# Microcontroller.net
KiCad netlist of a schematic drawn in Altium Designer
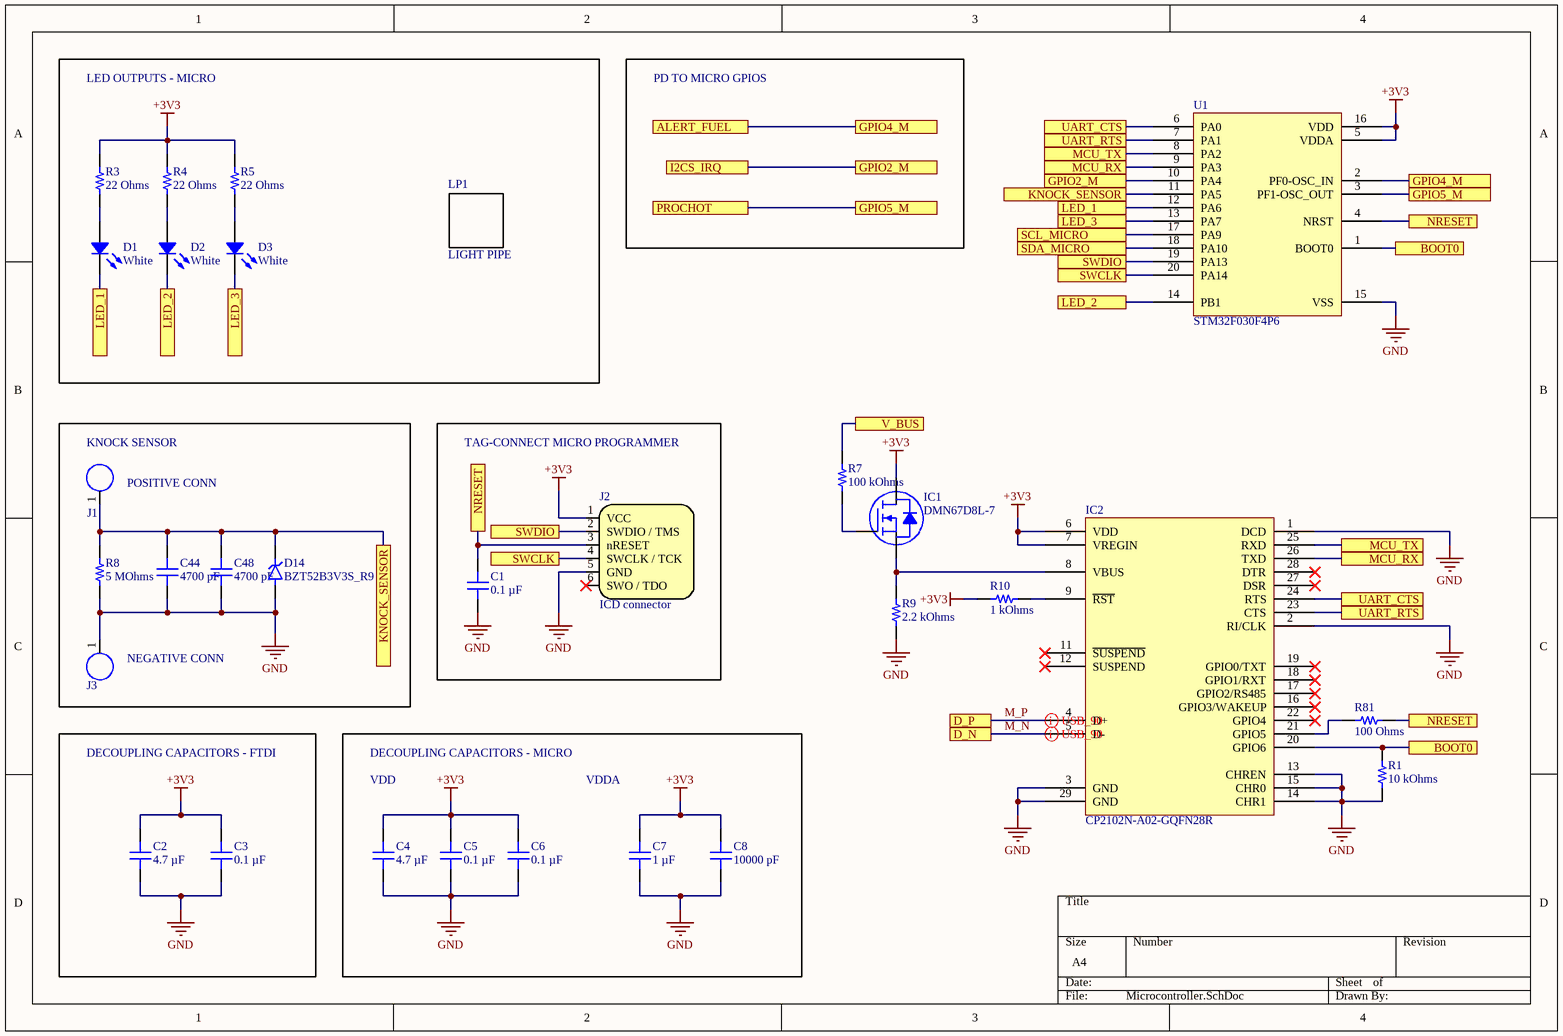
[diagram p0: Microcontroller.SchDoc]

(export (version "E")
  (design (tool "Eeschema 10.0.6"))
  (components
    (comp (ref "C1")
      (value "0.1 µF")
      (footprint "CAP 0402_1005")
      (description "CAP CER 0.1UF 10V X5R 0402")
      (fields (field (name "PART NUMBER") "LMK105BJ104MC-F") (field (name "MANUFACTURER") "Taiyo Yuden"))
      (libsource (lib "Celestial Altium Library - altium_library") (part "Capacitor"))
    )
    (comp (ref "C2")
      (value "4.7 µF")
      (footprint "CAP 0402_1005")
      (description "CAP CER 4.7UF 10V X5R 0402")
      (fields
        (field (name "PART NUMBER") "CL05A475KP5NRNC")
        (field (name "MANUFACTURER") "Samsung Electro-Mechanics")
      )
      (libsource (lib "Celestial Altium Library - altium_library") (part "Capacitor"))
    )
    (comp (ref "C3")
      (value "0.1 µF")
      (footprint "CAP 0402_1005")
      (description "CAP CER 0.1UF 10V X5R 0402")
      (fields (field (name "PART NUMBER") "LMK105BJ104MC-F") (field (name "MANUFACTURER") "Taiyo Yuden"))
      (libsource (lib "Celestial Altium Library - altium_library") (part "Capacitor"))
    )
    (comp (ref "C4")
      (value "4.7 µF")
      (footprint "CAP 0402_1005")
      (description "CAP CER 4.7UF 10V X5R 0402")
      (fields
        (field (name "PART NUMBER") "CL05A475KP5NRNC")
        (field (name "MANUFACTURER") "Samsung Electro-Mechanics")
      )
      (libsource (lib "Celestial Altium Library - altium_library") (part "Capacitor"))
    )
    (comp (ref "C5")
      (value "0.1 µF")
      (footprint "CAP 0402_1005")
      (description "CAP CER 0.1UF 10V X5R 0402")
      (fields (field (name "PART NUMBER") "LMK105BJ104MC-F") (field (name "MANUFACTURER") "Taiyo Yuden"))
      (libsource (lib "Celestial Altium Library - altium_library") (part "Capacitor"))
    )
    (comp (ref "C6")
      (value "0.1 µF")
      (footprint "CAP 0402_1005")
      (description "CAP CER 0.1UF 10V X5R 0402")
      (fields (field (name "PART NUMBER") "LMK105BJ104MC-F") (field (name "MANUFACTURER") "Taiyo Yuden"))
      (libsource (lib "Celestial Altium Library - altium_library") (part "Capacitor"))
    )
    (comp (ref "C7")
      (value "1 µF")
      (footprint "CAP 0402_1005")
      (description "CAP CER 1UF 10V X5R 0402")
      (fields (field (name "PART NUMBER") "LMK105BJ105KPLF") (field (name "MANUFACTURER") "Taiyo Yuden"))
      (libsource (lib "Celestial Altium Library - altium_library") (part "Capacitor"))
    )
    (comp (ref "C8")
      (value "10000 pF")
      (footprint "CAP 0402_1005")
      (description "CAP, MLCC, 0402/1005, 10V, X7R,")
      (fields (field (name "PART NUMBER") "LMF105B7103KVHF") (field (name "MANUFACTURER") "Taiyo Yuden"))
      (libsource (lib "Celestial Altium Library - altium_library") (part "Capacitor"))
    )
    (comp (ref "C44")
      (value "4700 pF")
      (footprint "CAP 0402_1005")
      (description "CAP CER 4700PF 50V X7R 0402")
      (fields
        (field (name "PART NUMBER") "0402B472J500CT")
        (field (name "MANUFACTURER") "Walsin Technology Corporation")
      )
      (libsource (lib "Celestial Altium Library - altium_library") (part "Capacitor"))
    )
    (comp (ref "C48")
      (value "4700 pF")
      (footprint "CAP 0402_1005")
      (description "CAP CER 4700PF 50V X7R 0402")
      (fields
        (field (name "PART NUMBER") "0402B472J500CT")
        (field (name "MANUFACTURER") "Walsin Technology Corporation")
      )
      (libsource (lib "Celestial Altium Library - altium_library") (part "Capacitor"))
    )
    (comp (ref "D1")
      (value "White")
      (footprint "LED 0805_2012")
      (description "0805 LED WHITE, YELLOW DIFFUSED")
      (fields (field (name "PART NUMBER") "QBLP631-IW5") (field (name "MANUFACTURER") "QT Brightek (QTB)"))
      (libsource (lib "Celestial Altium Library - altium_library") (part "LED"))
    )
    (comp (ref "D2")
      (value "White")
      (footprint "LED 0805_2012")
      (description "0805 LED WHITE, YELLOW DIFFUSED")
      (fields (field (name "PART NUMBER") "QBLP631-IW5") (field (name "MANUFACTURER") "QT Brightek (QTB)"))
      (libsource (lib "Celestial Altium Library - altium_library") (part "LED"))
    )
    (comp (ref "D3")
      (value "White")
      (footprint "LED 0805_2012")
      (description "0805 LED WHITE, YELLOW DIFFUSED")
      (fields (field (name "PART NUMBER") "QBLP631-IW5") (field (name "MANUFACTURER") "QT Brightek (QTB)"))
      (libsource (lib "Celestial Altium Library - altium_library") (part "LED"))
    )
    (comp (ref "D14")
      (value "BZT52B3V3S_R9")
      (footprint "BZT52B3V3S R9:DIO_BZT52B3V3S_R9")
      (fields (field (name "MF") "{'manufacturer': u'Taiwan Semiconductor'}"))
      (libsource (lib "*") (part "BZT52B3V3S_R9"))
    )
    (comp (ref "IC1")
      (value "DMN67D8L-7")
      (footprint "DIODES SOT-23-3")
      (description "MOSFET N-CH 60V 210MA SOT23")
      (fields (field (name "MANUFACTURER") "Diodes Incorporated"))
      (libsource (lib "Celestial Altium Library - altium_library") (part "DIODES INC MOSFET N-CH SOT-23-3"))
    )
    (comp (ref "IC2")
      (value "CP2102N-A02-GQFN28R")
      (footprint "SILICON LABS QFN-28 5x5MM")
      (description "IC USB TO UART BRIDGE QFN28")
      (fields (field (name "MANUFACTURER") "Silicon Labs"))
      (libsource (lib "Celestial Altium Library - altium_library") (part "Silicon Labs - CP2102N QFN28"))
    )
    (comp (ref "J1")
      (value "Large Board Solder Point")
      (footprint "Large Solder Point")
      (libsource (lib "Schlib2") (part "Large Board Solder Point"))
    )
    (comp (ref "J2")
      (value "ICD connector")
      (footprint "TC2030-MCP")
      (description "Conector par ICD")
      (libsource (lib "TC2030") (part "TC2030-MCP-NL"))
    )
    (comp (ref "J3")
      (value "Large Board Solder Point")
      (footprint "Large Solder Point")
      (libsource (lib "Schlib2") (part "Large Board Solder Point"))
    )
    (comp (ref "LP1")
      (value "LIGHT PIPE")
      (footprint "Dialight 515-1069F")
      (description "Light Pipe Dialight 515-1069F")
      (libsource (lib "Schlib2") (part "Dialight 515-1069F"))
    )
    (comp (ref "R1")
      (value "10 kOhms")
      (footprint "RES 0402_1005")
      (description "RES 10K OHM 5% 1/16W 0402")
      (fields (field (name "PART NUMBER") "RC0402JR-1310KL") (field (name "MANUFACTURER") "Yageo"))
      (libsource (lib "Celestial Altium Library - altium_library") (part "Resistor"))
    )
    (comp (ref "R3")
      (value "22 Ohms")
      (footprint "RES 1206_3216")
      (description "RES SMD 22 OHM 0.5% 1W 1206")
      (fields (field (name "PART NUMBER") "HRG3216Q-22R0-D-T1") (field (name "MANUFACTURER") "Susumu"))
      (libsource (lib "Celestial Altium Library - altium_library") (part "Resistor"))
    )
    (comp (ref "R4")
      (value "22 Ohms")
      (footprint "RES 1206_3216")
      (description "RES SMD 22 OHM 0.5% 1W 1206")
      (fields (field (name "PART NUMBER") "HRG3216Q-22R0-D-T1") (field (name "MANUFACTURER") "Susumu"))
      (libsource (lib "Celestial Altium Library - altium_library") (part "Resistor"))
    )
    (comp (ref "R5")
      (value "22 Ohms")
      (footprint "RES 1206_3216")
      (description "RES SMD 22 OHM 0.5% 1W 1206")
      (fields (field (name "PART NUMBER") "HRG3216Q-22R0-D-T1") (field (name "MANUFACTURER") "Susumu"))
      (libsource (lib "Celestial Altium Library - altium_library") (part "Resistor"))
    )
    (comp (ref "R7")
      (value "100 kOhms")
      (footprint "RES 0603_1608")
      (description "RES 100K OHM 0.1% 1/16W 0603")
      (fields
        (field (name "PART NUMBER") "RNCS0603BKE100K")
        (field (name "MANUFACTURER") "Stackpole Electronics Inc")
      )
      (libsource (lib "Celestial Altium Library - altium_library") (part "Resistor"))
    )
    (comp (ref "R8")
      (value "5 MOhms")
      (footprint "RES 0603_1608")
      (description "RES SMD 5M OHM 1% 1/10W 0603")
      (fields (field (name "PART NUMBER") "HVC0603T5004FET") (field (name "MANUFACTURER") "Ohmite"))
      (libsource (lib "Celestial Altium Library - altium_library") (part "Resistor"))
    )
    (comp (ref "R9")
      (value "2.2 kOhms")
      (footprint "RES 0402_1005")
      (description "RES 2.2K OHM 0.1% 1/10W 0402")
      (fields (field (name "PART NUMBER") "TNPW04022K20BYEP") (field (name "MANUFACTURER") "Vishay Dale"))
      (libsource (lib "Celestial Altium Library - altium_library") (part "Resistor"))
    )
    (comp (ref "R10")
      (value "1 kOhms")
      (footprint "RES 0402_1005")
      (description "RES SMD 1K OHM 5% 1/16W 0402")
      (fields (field (name "PART NUMBER") "AF0402JR-071KL") (field (name "MANUFACTURER") "Yageo"))
      (libsource (lib "Celestial Altium Library - altium_library") (part "Resistor"))
    )
    (comp (ref "R81")
      (value "100 Ohms")
      (footprint "RES 0402_1005")
      (description "RES 100 OHM 0.5% 1/5W 0402")
      (fields
        (field (name "PART NUMBER") "MCS0402PD1000DE500")
        (field (name "MANUFACTURER") "Vishay Beyschlag")
      )
      (libsource (lib "Celestial Altium Library - altium_library") (part "Resistor"))
    )
    (comp (ref "U1")
      (value "STM32F030F4P6")
      (footprint "TSOP65P640X120-20N")
      (libsource (lib "Schlib2") (part "STM32F030F4P6"))
    )
  )
  (nets
    (net (code "1") (name "+3V3") (class "Default")
      (node (ref "C2") (pin "2") (pinfunction "2_2") (pintype "passive"))
      (node (ref "C3") (pin "2") (pinfunction "2_2") (pintype "passive"))
      (node (ref "C4") (pin "2") (pinfunction "2_2") (pintype "passive"))
      (node (ref "C5") (pin "2") (pinfunction "2_2") (pintype "passive"))
      (node (ref "C6") (pin "2") (pinfunction "2_2") (pintype "passive"))
      (node (ref "C7") (pin "2") (pinfunction "2_2") (pintype "passive"))
      (node (ref "C8") (pin "2") (pinfunction "2_2") (pintype "passive"))
      (node (ref "IC1") (pin "3") (pinfunction "D_3") (pintype "passive"))
      (node (ref "IC2") (pin "6") (pinfunction "VDD_6") (pintype "passive"))
      (node (ref "IC2") (pin "7") (pinfunction "VREGIN_7") (pintype "passive"))
      (node (ref "J2") (pin "1") (pinfunction "VCC_1") (pintype "passive"))
      (node (ref "R10") (pin "1") (pinfunction "1_1") (pintype "passive"))
      (node (ref "R3") (pin "2") (pinfunction "2_2") (pintype "passive"))
      (node (ref "R4") (pin "2") (pinfunction "2_2") (pintype "passive"))
      (node (ref "R5") (pin "2") (pinfunction "2_2") (pintype "passive"))
      (node (ref "U1") (pin "16") (pinfunction "VDD_16") (pintype "passive"))
      (node (ref "U1") (pin "5") (pinfunction "VDDA_5") (pintype "passive"))
    )
    (net (code "2") (name "/ALERT_FUEL") (class "Default")
      (node (ref "U1") (pin "2") (pinfunction "PF0-OSC_IN_2") (pintype "passive"))
    )
    (net (code "3") (name "/BOOT0") (class "Default")
      (node (ref "IC2") (pin "20") (pinfunction "GPIO6_20") (pintype "passive"))
      (node (ref "R1") (pin "1") (pinfunction "1_1") (pintype "passive"))
      (node (ref "U1") (pin "1") (pinfunction "BOOT0_1") (pintype "passive"))
    )
    (net (code "4") (name "/GPIO2_M") (class "Default")
      (node (ref "U1") (pin "10") (pinfunction "PA4_10") (pintype "passive"))
    )
    (net (code "5") (name "/GPIO5_M") (class "Default")
      (node (ref "U1") (pin "3") (pinfunction "PF1-OSC_OUT_3") (pintype "passive"))
    )
    (net (code "6") (name "/KNOCK_SENSOR") (class "Default")
      (node (ref "C44") (pin "2") (pinfunction "2_2") (pintype "passive"))
      (node (ref "C48") (pin "2") (pinfunction "2_2") (pintype "passive"))
      (node (ref "D14") (pin "C") (pinfunction "K_C") (pintype "passive"))
      (node (ref "J1") (pin "1") (pintype "passive"))
      (node (ref "R8") (pin "2") (pinfunction "2_2") (pintype "passive"))
      (node (ref "U1") (pin "11") (pinfunction "PA5_11") (pintype "passive"))
    )
    (net (code "7") (name "/LED_1") (class "Default")
      (node (ref "D1") (pin "2") (pinfunction "2_2") (pintype "passive"))
      (node (ref "U1") (pin "12") (pinfunction "PA6_12") (pintype "passive"))
    )
    (net (code "8") (name "/LED_2") (class "Default")
      (node (ref "D2") (pin "2") (pinfunction "2_2") (pintype "passive"))
      (node (ref "U1") (pin "14") (pinfunction "PB1_14") (pintype "passive"))
    )
    (net (code "9") (name "/LED_3") (class "Default")
      (node (ref "D3") (pin "2") (pinfunction "2_2") (pintype "passive"))
      (node (ref "U1") (pin "13") (pinfunction "PA7_13") (pintype "passive"))
    )
    (net (code "10") (name "/MCU_RX") (class "Default")
      (node (ref "IC2") (pin "26") (pinfunction "TXD_26") (pintype "passive"))
      (node (ref "U1") (pin "9") (pinfunction "PA3_9") (pintype "passive"))
    )
    (net (code "11") (name "/MCU_TX") (class "Default")
      (node (ref "IC2") (pin "25") (pinfunction "RXD_25") (pintype "passive"))
      (node (ref "U1") (pin "8") (pinfunction "PA2_8") (pintype "passive"))
    )
    (net (code "12") (name "/M_N") (class "Default")
      (node (ref "IC2") (pin "5") (pinfunction "D-_5") (pintype "passive"))
    )
    (net (code "13") (name "/M_P") (class "Default")
      (node (ref "IC2") (pin "4") (pinfunction "D+_4") (pintype "passive"))
    )
    (net (code "14") (name "/NRESET") (class "Default")
      (node (ref "C1") (pin "2") (pinfunction "2_2") (pintype "passive"))
      (node (ref "J2") (pin "3") (pinfunction "nRESET_3") (pintype "passive"))
      (node (ref "R81") (pin "2") (pinfunction "2_2") (pintype "passive"))
      (node (ref "U1") (pin "4") (pinfunction "NRST_4") (pintype "passive"))
    )
    (net (code "15") (name "/SCL_MICRO") (class "Default")
      (node (ref "U1") (pin "17") (pinfunction "PA9_17") (pintype "passive"))
    )
    (net (code "16") (name "/SDA_MICRO") (class "Default")
      (node (ref "U1") (pin "18") (pinfunction "PA10_18") (pintype "passive"))
    )
    (net (code "17") (name "/SWCLK") (class "Default")
      (node (ref "J2") (pin "4") (pinfunction "SWCLK_/_TCK_4") (pintype "passive"))
      (node (ref "U1") (pin "20") (pinfunction "PA14_20") (pintype "passive"))
    )
    (net (code "18") (name "/SWDIO") (class "Default")
      (node (ref "J2") (pin "2") (pinfunction "SWDIO_/_TMS_2") (pintype "passive"))
      (node (ref "U1") (pin "19") (pinfunction "PA13_19") (pintype "passive"))
    )
    (net (code "19") (name "/UART_CTS") (class "Default")
      (node (ref "IC2") (pin "24") (pinfunction "RTS_24") (pintype "passive"))
      (node (ref "U1") (pin "6") (pinfunction "PA0_6") (pintype "passive"))
    )
    (net (code "20") (name "/UART_RTS") (class "Default")
      (node (ref "IC2") (pin "23") (pinfunction "CTS_23") (pintype "passive"))
      (node (ref "U1") (pin "7") (pinfunction "PA1_7") (pintype "passive"))
    )
    (net (code "21") (name "/V_BUS") (class "Default")
      (node (ref "R7") (pin "2") (pinfunction "2_2") (pintype "passive"))
    )
    (net (code "22") (name "GND") (class "Default")
      (node (ref "C1") (pin "1") (pinfunction "1_1") (pintype "passive"))
      (node (ref "C2") (pin "1") (pinfunction "1_1") (pintype "passive"))
      (node (ref "C3") (pin "1") (pinfunction "1_1") (pintype "passive"))
      (node (ref "C4") (pin "1") (pinfunction "1_1") (pintype "passive"))
      (node (ref "C44") (pin "1") (pinfunction "1_1") (pintype "passive"))
      (node (ref "C48") (pin "1") (pinfunction "1_1") (pintype "passive"))
      (node (ref "C5") (pin "1") (pinfunction "1_1") (pintype "passive"))
      (node (ref "C6") (pin "1") (pinfunction "1_1") (pintype "passive"))
      (node (ref "C7") (pin "1") (pinfunction "1_1") (pintype "passive"))
      (node (ref "C8") (pin "1") (pinfunction "1_1") (pintype "passive"))
      (node (ref "D14") (pin "A") (pinfunction "A_A") (pintype "passive"))
      (node (ref "IC2") (pin "1") (pinfunction "DCD_1") (pintype "passive"))
      (node (ref "IC2") (pin "13") (pinfunction "CHREN_13") (pintype "passive"))
      (node (ref "IC2") (pin "14") (pinfunction "CHR1_14") (pintype "passive"))
      (node (ref "IC2") (pin "15") (pinfunction "CHR0_15") (pintype "passive"))
      (node (ref "IC2") (pin "2") (pinfunction "RI/CLK_2") (pintype "passive"))
      (node (ref "IC2") (pin "29") (pinfunction "GND_29") (pintype "passive"))
      (node (ref "IC2") (pin "3") (pinfunction "GND_3") (pintype "passive"))
      (node (ref "J2") (pin "5") (pinfunction "GND_5") (pintype "passive"))
      (node (ref "J3") (pin "1") (pintype "passive"))
      (node (ref "R1") (pin "2") (pinfunction "2_2") (pintype "passive"))
      (node (ref "R8") (pin "1") (pinfunction "1_1") (pintype "passive"))
      (node (ref "R9") (pin "1") (pinfunction "1_1") (pintype "passive"))
      (node (ref "U1") (pin "15") (pinfunction "VSS_15") (pintype "passive"))
    )
    (net (code "23") (name "Net-(D1-Pad1)") (class "Default")
      (node (ref "D1") (pin "1") (pinfunction "1_1") (pintype "passive"))
      (node (ref "R3") (pin "1") (pinfunction "1_1") (pintype "passive"))
    )
    (net (code "24") (name "Net-(D2-Pad1)") (class "Default")
      (node (ref "D2") (pin "1") (pinfunction "1_1") (pintype "passive"))
      (node (ref "R4") (pin "1") (pinfunction "1_1") (pintype "passive"))
    )
    (net (code "25") (name "Net-(D3-Pad1)") (class "Default")
      (node (ref "D3") (pin "1") (pinfunction "1_1") (pintype "passive"))
      (node (ref "R5") (pin "1") (pinfunction "1_1") (pintype "passive"))
    )
    (net (code "26") (name "Net-(IC1-G)") (class "Default")
      (node (ref "IC1") (pin "1") (pinfunction "G_1") (pintype "passive"))
      (node (ref "R7") (pin "1") (pinfunction "1_1") (pintype "passive"))
    )
    (net (code "27") (name "Net-(IC1-S)") (class "Default")
      (node (ref "IC1") (pin "2") (pinfunction "S_2") (pintype "passive"))
      (node (ref "IC2") (pin "8") (pinfunction "VBUS_8") (pintype "passive"))
      (node (ref "R9") (pin "2") (pinfunction "2_2") (pintype "passive"))
    )
    (net (code "28") (name "Net-(IC2-GPIO5)") (class "Default")
      (node (ref "IC2") (pin "21") (pinfunction "GPIO5_21") (pintype "passive"))
      (node (ref "R81") (pin "1") (pinfunction "1_1") (pintype "passive"))
    )
    (net (code "29") (name "Net-(IC2-~{RST})") (class "Default")
      (node (ref "IC2") (pin "9") (pinfunction "~{RST}_9") (pintype "passive"))
      (node (ref "R10") (pin "2") (pinfunction "2_2") (pintype "passive"))
    )
    (net (code "30") (name "unconnected-(IC2-DSR-Pad27)") (class "Default")
      (node (ref "IC2") (pin "27") (pinfunction "DSR_27") (pintype "passive+no_connect"))
    )
    (net (code "31") (name "unconnected-(IC2-DTR-Pad28)") (class "Default")
      (node (ref "IC2") (pin "28") (pinfunction "DTR_28") (pintype "passive+no_connect"))
    )
    (net (code "32") (name "unconnected-(IC2-GPIO0{slash}TXT-Pad19)") (class "Default")
      (node (ref "IC2") (pin "19") (pinfunction "GPIO0/TXT_19") (pintype "passive+no_connect"))
    )
    (net (code "33") (name "unconnected-(IC2-GPIO1{slash}RXT-Pad18)") (class "Default")
      (node (ref "IC2") (pin "18") (pinfunction "GPIO1/RXT_18") (pintype "passive+no_connect"))
    )
    (net (code "34") (name "unconnected-(IC2-GPIO2{slash}RS485-Pad17)") (class "Default")
      (node (ref "IC2") (pin "17") (pinfunction "GPIO2/RS485_17") (pintype "passive+no_connect"))
    )
    (net (code "35") (name "unconnected-(IC2-GPIO3{slash}WAKEUP-Pad16)") (class "Default")
      (node (ref "IC2") (pin "16") (pinfunction "GPIO3/WAKEUP_16") (pintype "passive+no_connect"))
    )
    (net (code "36") (name "unconnected-(IC2-GPIO4-Pad22)") (class "Default")
      (node (ref "IC2") (pin "22") (pinfunction "GPIO4_22") (pintype "passive+no_connect"))
    )
    (net (code "37") (name "unconnected-(IC2-SUSPEND-Pad12)") (class "Default")
      (node (ref "IC2") (pin "12") (pinfunction "SUSPEND_12") (pintype "passive+no_connect"))
    )
    (net (code "38") (name "unconnected-(IC2-~{SUSPEND}-Pad11)") (class "Default")
      (node (ref "IC2") (pin "11") (pinfunction "~{SUSPEND}_11") (pintype "passive+no_connect"))
    )
    (net (code "39") (name "unconnected-(J2-SWO_{slash}_TDO-Pad6)") (class "Default")
      (node (ref "J2") (pin "6") (pinfunction "SWO_/_TDO_6") (pintype "passive+no_connect"))
    )
  )
)
